# AudioReceiver.net
KiCad netlist of a schematic drawn in EAGLE
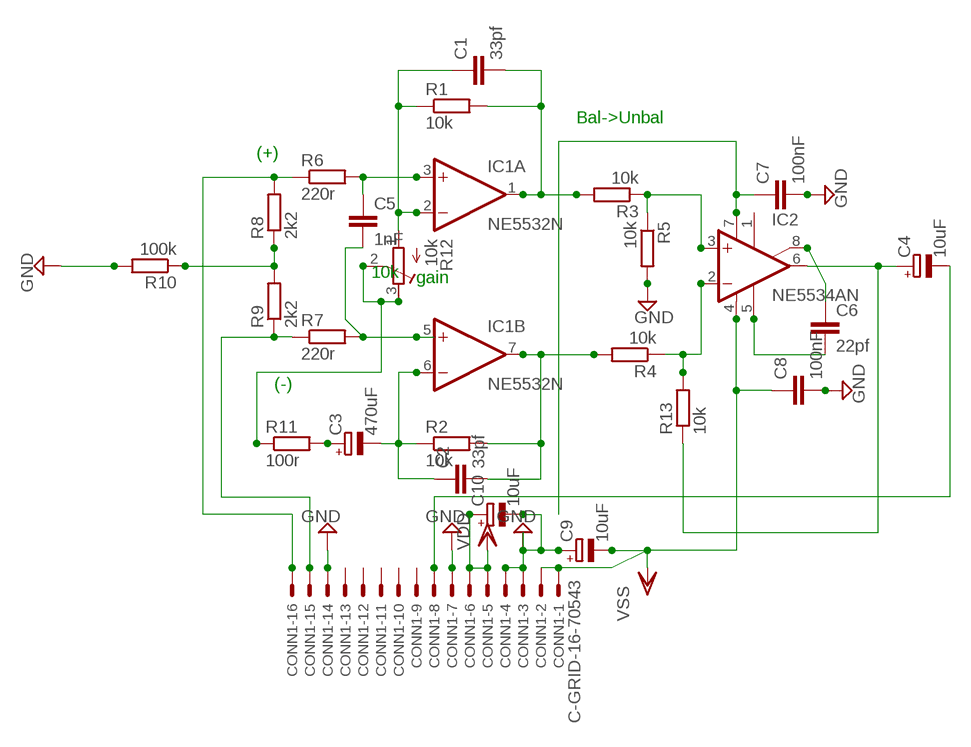
[diagram p0: schematic, sheet 1]

(export (version "E")
  (design (tool "Eeschema 10.0.6"))
  (components
    (comp (ref "C1")
      (value "33pf")
      (footprint "eagle-import:C2.5-2")
      (libsource (lib "eagle-import") (part "C2.5/2"))
    )
    (comp (ref "C2")
      (value "33pf")
      (footprint "eagle-import:C2.5-2")
      (libsource (lib "eagle-import") (part "C2.5/2"))
    )
    (comp (ref "C3")
      (value "470uF")
      (footprint "eagle-import:E5-10,5")
      (libsource (lib "eagle-import") (part "CPOL-EUE5-10.5"))
    )
    (comp (ref "C4")
      (value "10uF")
      (footprint "eagle-import:E2,5-5")
      (libsource (lib "eagle-import") (part "CPOL-EUE2.5-5"))
    )
    (comp (ref "C5")
      (value "1nF")
      (footprint "eagle-import:C5B2.5")
      (libsource (lib "eagle-import") (part "C5/2.5"))
    )
    (comp (ref "C6")
      (value "22pf")
      (footprint "eagle-import:C2.5-2")
      (libsource (lib "eagle-import") (part "C2.5/2"))
    )
    (comp (ref "C7")
      (value "100nF")
      (footprint "eagle-import:C5B2.5")
      (libsource (lib "eagle-import") (part "C5/2.5"))
    )
    (comp (ref "C8")
      (value "100nF")
      (footprint "eagle-import:C5B2.5")
      (libsource (lib "eagle-import") (part "C5/2.5"))
    )
    (comp (ref "C9")
      (value "10uF")
      (footprint "eagle-import:E2,5-5")
      (libsource (lib "eagle-import") (part "resistor_CPOL-EUE2.5-5"))
    )
    (comp (ref "C10")
      (value "10uF")
      (footprint "eagle-import:E2,5-5")
      (libsource (lib "eagle-import") (part "resistor_CPOL-EUE2.5-5"))
    )
    (comp (ref "CONN1")
      (value "C-GRID-16-70543")
      (footprint "eagle-import:70543-16")
      (libsource (lib "eagle-import") (part "C-GRID-16-70543"))
    )
    (comp (ref "IC1")
      (value "NE5532N")
      (footprint "eagle-import:DIL08")
      (libsource (lib "eagle-import") (part "NE5532N"))
    )
    (comp (ref "IC2")
      (value "NE5534AN")
      (footprint "eagle-import:DIL08")
      (libsource (lib "eagle-import") (part "NE5534NA"))
    )
    (comp (ref "R1")
      (value "10k")
      (footprint "eagle-import:0204_7")
      (libsource (lib "eagle-import") (part "R-EU_0204/7"))
    )
    (comp (ref "R2")
      (value "10k")
      (footprint "eagle-import:0204_7")
      (libsource (lib "eagle-import") (part "R-EU_0204/7"))
    )
    (comp (ref "R3")
      (value "10k")
      (footprint "eagle-import:0204_7")
      (libsource (lib "eagle-import") (part "R-EU_0204/7"))
    )
    (comp (ref "R4")
      (value "10k")
      (footprint "eagle-import:0204_7")
      (libsource (lib "eagle-import") (part "R-EU_0204/7"))
    )
    (comp (ref "R5")
      (value "10k")
      (footprint "eagle-import:0204_7")
      (libsource (lib "eagle-import") (part "R-EU_0204/7"))
    )
    (comp (ref "R6")
      (value "220r")
      (footprint "eagle-import:0204_7")
      (libsource (lib "eagle-import") (part "R-EU_0204/7"))
    )
    (comp (ref "R7")
      (value "220r")
      (footprint "eagle-import:0204_7")
      (libsource (lib "eagle-import") (part "R-EU_0204/7"))
    )
    (comp (ref "R8")
      (value "2k2")
      (footprint "eagle-import:0204_7")
      (libsource (lib "eagle-import") (part "R-EU_0204/7"))
    )
    (comp (ref "R9")
      (value "2k2")
      (footprint "eagle-import:0204_7")
      (libsource (lib "eagle-import") (part "R-EU_0204/7"))
    )
    (comp (ref "R10")
      (value "100k")
      (footprint "eagle-import:0204_7")
      (libsource (lib "eagle-import") (part "R-EU_0204/7"))
    )
    (comp (ref "R11")
      (value "100r")
      (footprint "eagle-import:0204_7")
      (libsource (lib "eagle-import") (part "R-EU_0204/7"))
    )
    (comp (ref "R12")
      (value "10k")
      (footprint "eagle-import:RTRIM64P")
      (fields (field (name "TRIM1") "10k"))
      (libsource (lib "eagle-import") (part "R-TRIMM64P"))
    )
    (comp (ref "R13")
      (value "10k")
      (footprint "eagle-import:0204_7")
      (libsource (lib "eagle-import") (part "R-EU_0204/7"))
    )
  )
  (nets
    (net (code "1") (name "GND") (class "Default")
      (node (ref "C10") (pin "-") (pinfunction "-_-") (pintype "passive"))
      (node (ref "C7") (pin "2") (pinfunction "2_2") (pintype "passive"))
      (node (ref "C8") (pin "2") (pinfunction "2_2") (pintype "passive"))
      (node (ref "C9") (pin "+") (pinfunction "+_+") (pintype "passive"))
      (node (ref "CONN1") (pin "14") (pinfunction "S_14") (pintype "passive"))
      (node (ref "CONN1") (pin "3") (pinfunction "S_3") (pintype "passive"))
      (node (ref "CONN1") (pin "4") (pinfunction "S_4") (pintype "passive"))
      (node (ref "CONN1") (pin "7") (pinfunction "S_7") (pintype "passive"))
      (node (ref "R10") (pin "2") (pinfunction "2_2") (pintype "passive"))
      (node (ref "R5") (pin "2") (pinfunction "2_2") (pintype "passive"))
    )
    (net (code "2") (name "Net-(C3-Pad+)") (class "Default")
      (node (ref "C3") (pin "+") (pinfunction "+_+") (pintype "passive"))
      (node (ref "R11") (pin "2") (pinfunction "2_2") (pintype "passive"))
    )
    (net (code "3") (name "Net-(CONN1G-S)") (class "Default")
      (node (ref "CONN1") (pin "15") (pinfunction "S_15") (pintype "passive"))
      (node (ref "R7") (pin "1") (pinfunction "1_1") (pintype "passive"))
      (node (ref "R9") (pin "1") (pinfunction "1_1") (pintype "passive"))
    )
    (net (code "4") (name "Net-(CONN1H-S)") (class "Default")
      (node (ref "CONN1") (pin "16") (pinfunction "S_16") (pintype "passive"))
      (node (ref "R6") (pin "1") (pinfunction "1_1") (pintype "passive"))
      (node (ref "R8") (pin "2") (pinfunction "2_2") (pintype "passive"))
    )
    (net (code "5") (name "Net-(CONN1O-S)") (class "Default")
      (node (ref "C4") (pin "-") (pinfunction "-_-") (pintype "passive"))
      (node (ref "CONN1") (pin "8") (pinfunction "S_8") (pintype "passive"))
    )
    (net (code "6") (name "Net-(IC1A-+IN)") (class "Default")
      (node (ref "C5") (pin "1") (pinfunction "1_1") (pintype "passive"))
      (node (ref "IC1") (pin "3") (pinfunction "+IN_3") (pintype "input"))
      (node (ref "R6") (pin "2") (pinfunction "2_2") (pintype "passive"))
    )
    (net (code "7") (name "Net-(IC1A--IN)") (class "Default")
      (node (ref "C1") (pin "1") (pinfunction "1_1") (pintype "passive"))
      (node (ref "IC1") (pin "2") (pinfunction "-IN_2") (pintype "input"))
      (node (ref "R1") (pin "1") (pinfunction "1_1") (pintype "passive"))
      (node (ref "R12") (pin "1") (pinfunction "A_1") (pintype "passive"))
    )
    (net (code "8") (name "Net-(IC1A-OUT)") (class "Default")
      (node (ref "C1") (pin "2") (pinfunction "2_2") (pintype "passive"))
      (node (ref "IC1") (pin "1") (pinfunction "OUT_1") (pintype "output"))
      (node (ref "R1") (pin "2") (pinfunction "2_2") (pintype "passive"))
      (node (ref "R3") (pin "2") (pinfunction "2_2") (pintype "passive"))
    )
    (net (code "9") (name "Net-(IC1B-+IN)") (class "Default")
      (node (ref "C5") (pin "2") (pinfunction "2_2") (pintype "passive"))
      (node (ref "IC1") (pin "5") (pinfunction "+IN_5") (pintype "input"))
      (node (ref "R7") (pin "2") (pinfunction "2_2") (pintype "passive"))
    )
    (net (code "10") (name "Net-(IC1B--IN)") (class "Default")
      (node (ref "C2") (pin "1") (pinfunction "1_1") (pintype "passive"))
      (node (ref "C3") (pin "-") (pinfunction "-_-") (pintype "passive"))
      (node (ref "IC1") (pin "6") (pinfunction "-IN_6") (pintype "input"))
      (node (ref "R2") (pin "1") (pinfunction "1_1") (pintype "passive"))
    )
    (net (code "11") (name "Net-(IC1B-OUT)") (class "Default")
      (node (ref "C2") (pin "2") (pinfunction "2_2") (pintype "passive"))
      (node (ref "IC1") (pin "7") (pinfunction "OUT_7") (pintype "output"))
      (node (ref "R2") (pin "2") (pinfunction "2_2") (pintype "passive"))
      (node (ref "R4") (pin "2") (pinfunction "2_2") (pintype "passive"))
    )
    (net (code "12") (name "Net-(IC2-+IN)") (class "Default")
      (node (ref "IC2") (pin "3") (pinfunction "+IN_3") (pintype "input"))
      (node (ref "R3") (pin "1") (pinfunction "1_1") (pintype "passive"))
      (node (ref "R5") (pin "1") (pinfunction "1_1") (pintype "passive"))
    )
    (net (code "13") (name "Net-(IC2--IN)") (class "Default")
      (node (ref "IC2") (pin "2") (pinfunction "-IN_2") (pintype "input"))
      (node (ref "R13") (pin "2") (pinfunction "2_2") (pintype "passive"))
      (node (ref "R4") (pin "1") (pinfunction "1_1") (pintype "passive"))
    )
    (net (code "14") (name "Net-(IC2-CMP)") (class "Default")
      (node (ref "C6") (pin "2") (pinfunction "2_2") (pintype "passive"))
      (node (ref "IC2") (pin "5") (pinfunction "CMP_5") (pintype "passive"))
    )
    (net (code "15") (name "Net-(IC2-ON{slash}CMP)") (class "Default")
      (node (ref "C6") (pin "1") (pinfunction "1_1") (pintype "passive"))
      (node (ref "IC2") (pin "8") (pinfunction "ON/CMP_8") (pintype "passive"))
    )
    (net (code "16") (name "Net-(IC2-OUT)") (class "Default")
      (node (ref "C4") (pin "+") (pinfunction "+_+") (pintype "passive"))
      (node (ref "IC2") (pin "6") (pinfunction "OUT_6") (pintype "output"))
      (node (ref "R13") (pin "1") (pinfunction "1_1") (pintype "passive"))
    )
    (net (code "17") (name "Net-(R10-Pad1)") (class "Default")
      (node (ref "R10") (pin "1") (pinfunction "1_1") (pintype "passive"))
      (node (ref "R8") (pin "1") (pinfunction "1_1") (pintype "passive"))
      (node (ref "R9") (pin "2") (pinfunction "2_2") (pintype "passive"))
    )
    (net (code "18") (name "Net-(R12-E)") (class "Default")
      (node (ref "R11") (pin "1") (pinfunction "1_1") (pintype "passive"))
      (node (ref "R12") (pin "2") (pinfunction "S_2") (pintype "passive"))
      (node (ref "R12") (pin "3") (pinfunction "E_3") (pintype "passive"))
    )
    (net (code "19") (name "VDD") (class "Default")
      (node (ref "C10") (pin "+") (pinfunction "+_+") (pintype "passive"))
      (node (ref "C7") (pin "1") (pinfunction "1_1") (pintype "passive"))
      (node (ref "CONN1") (pin "5") (pinfunction "S_5") (pintype "passive"))
      (node (ref "CONN1") (pin "6") (pinfunction "S_6") (pintype "passive"))
      (node (ref "IC2") (pin "7") (pinfunction "V+_7") (pintype "power_in"))
    )
    (net (code "20") (name "VSS") (class "Default")
      (node (ref "C8") (pin "1") (pinfunction "1_1") (pintype "passive"))
      (node (ref "C9") (pin "-") (pinfunction "-_-") (pintype "passive"))
      (node (ref "CONN1") (pin "1") (pinfunction "S_1") (pintype "passive"))
      (node (ref "CONN1") (pin "2") (pinfunction "S_2") (pintype "passive"))
      (node (ref "IC2") (pin "4") (pinfunction "V-_4") (pintype "power_in"))
    )
    (net (code "21") (name "unconnected-(CONN1B-S-Pad10)") (class "Default")
      (node (ref "CONN1") (pin "10") (pinfunction "S_10") (pintype "passive"))
    )
    (net (code "22") (name "unconnected-(CONN1C-S-Pad11)") (class "Default")
      (node (ref "CONN1") (pin "11") (pinfunction "S_11") (pintype "passive"))
    )
    (net (code "23") (name "unconnected-(CONN1D-S-Pad12)") (class "Default")
      (node (ref "CONN1") (pin "12") (pinfunction "S_12") (pintype "passive"))
    )
    (net (code "24") (name "unconnected-(CONN1E-S-Pad13)") (class "Default")
      (node (ref "CONN1") (pin "13") (pinfunction "S_13") (pintype "passive"))
    )
    (net (code "25") (name "unconnected-(CONN1P-S-Pad9)") (class "Default")
      (node (ref "CONN1") (pin "9") (pinfunction "S_9") (pintype "passive"))
    )
    (net (code "26") (name "unconnected-(IC2-ON-Pad1)") (class "Default")
      (node (ref "IC2") (pin "1") (pinfunction "ON_1") (pintype "passive"))
    )
  )
)
